# coqui-v0_2.net
KiCad netlist of a schematic drawn in EAGLE
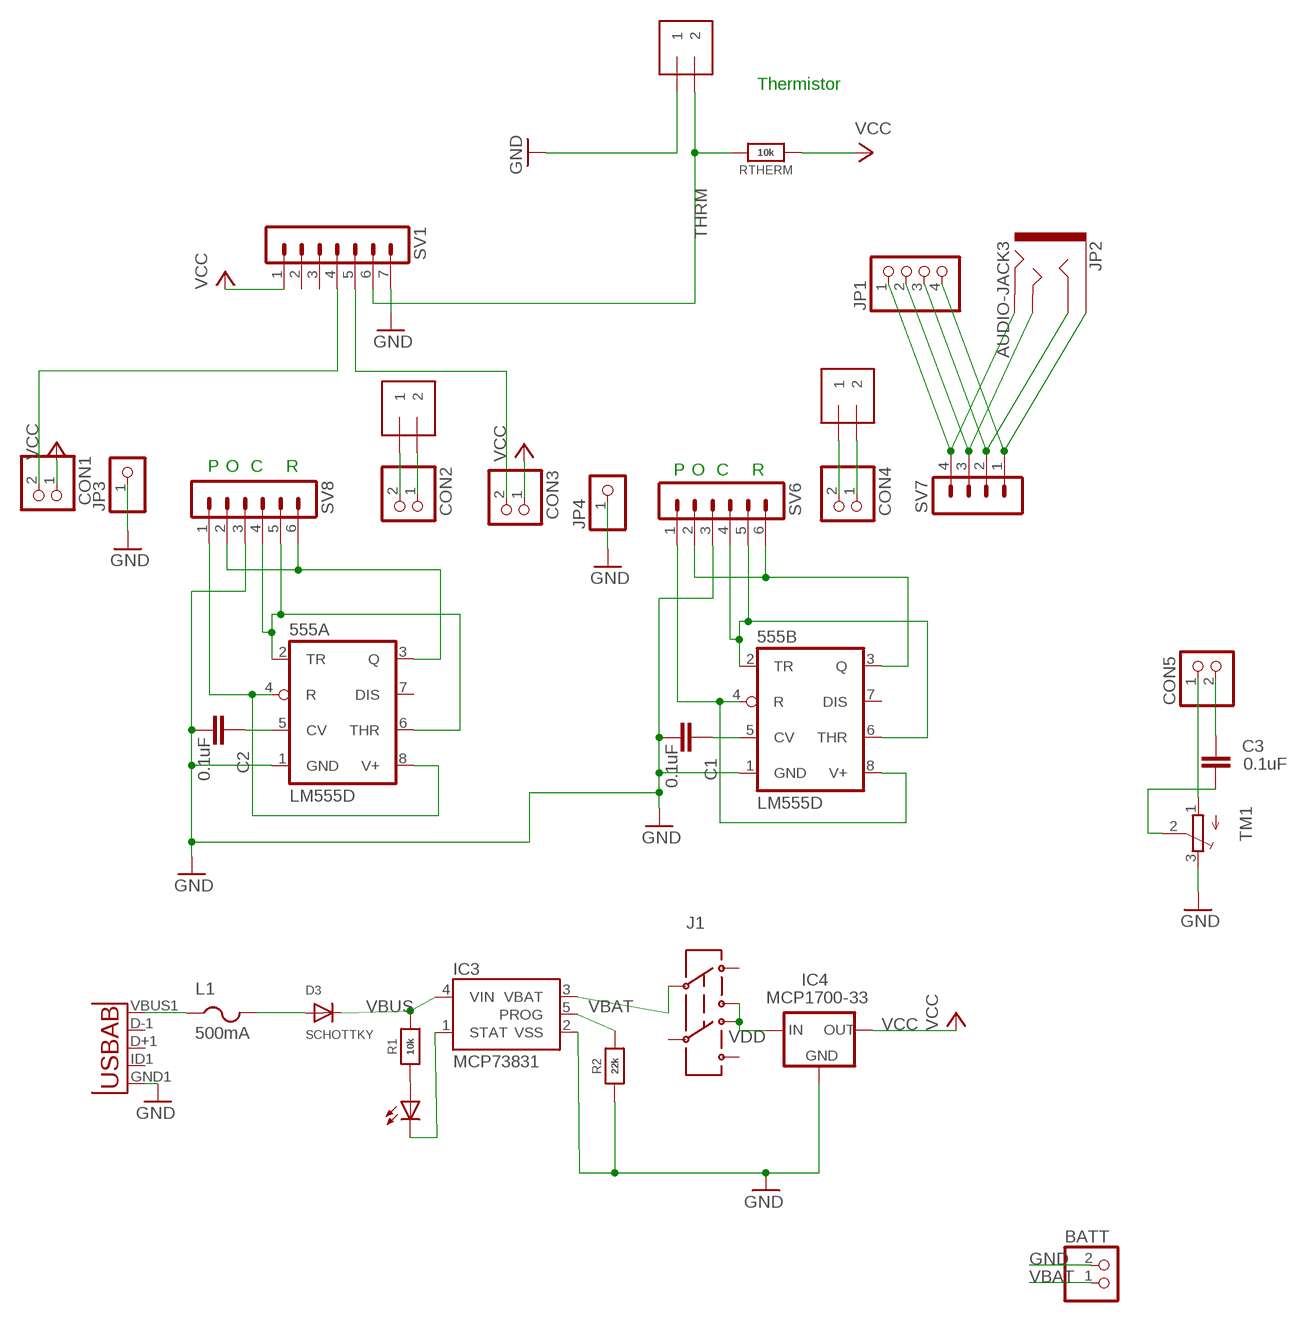
[diagram p0: schematic, sheet 1]

(export (version "E")
  (design (tool "Eeschema 10.0.6"))
  (components
    (comp (ref "555A")
      (value "LM555D")
      (footprint "eagle-import:SO08")
      (libsource (lib "eagle-import") (part "555DLM"))
    )
    (comp (ref "555B")
      (value "LM555D")
      (footprint "eagle-import:SO08")
      (libsource (lib "eagle-import") (part "555DLM"))
    )
    (comp (ref "BATT")
      (value "JST_2PIN-SMT-RA")
      (footprint "eagle-import:JST-PH-2-SMT-RA")
      (libsource (lib "eagle-import") (part "JST_2PIN-SMT-RA"))
    )
    (comp (ref "C1")
      (value "0.1uF")
      (footprint "eagle-import:0603-CAP")
      (libsource (lib "eagle-import") (part "CAP0603-CAP"))
    )
    (comp (ref "C2")
      (value "0.1uF")
      (footprint "eagle-import:0603-CAP")
      (libsource (lib "eagle-import") (part "CAP0603-CAP"))
    )
    (comp (ref "C3")
      (value "0.1uF")
      (footprint "eagle-import:0603-CAP")
      (libsource (lib "eagle-import") (part "CAP0603-CAP"))
    )
    (comp (ref "CHG")
      (value "0805")
      (footprint "eagle-import:CHIPLED_0805")
      (libsource (lib "eagle-import") (part "LEDCHIPLED_0805"))
    )
    (comp (ref "CON1")
      (value "PINHD-1X2")
      (footprint "eagle-import:1X02")
      (libsource (lib "eagle-import") (part "PINHD-1X2"))
    )
    (comp (ref "CON2")
      (value "PINHD-1X2")
      (footprint "eagle-import:1X02")
      (libsource (lib "eagle-import") (part "PINHD-1X2"))
    )
    (comp (ref "CON3")
      (value "PINHD-1X2")
      (footprint "eagle-import:1X02")
      (libsource (lib "eagle-import") (part "PINHD-1X2"))
    )
    (comp (ref "CON4")
      (value "PINHD-1X2")
      (footprint "eagle-import:1X02")
      (libsource (lib "eagle-import") (part "PINHD-1X2"))
    )
    (comp (ref "CON5")
      (value "PINHD-1X2")
      (footprint "eagle-import:1X02")
      (libsource (lib "eagle-import") (part "PINHD-1X2"))
    )
    (comp (ref "D3")
      (value "SCHOTTKY")
      (footprint "eagle-import:SOD-123FL")
      (libsource (lib "eagle-import") (part "DIODE_SOD-123FL"))
    )
    (comp (ref "IC3")
      (value "MCP73831")
      (footprint "eagle-import:SOT23-5")
      (libsource (lib "eagle-import") (part "MCP73831"))
    )
    (comp (ref "IC4")
      (value "MCP1700-33")
      (footprint "eagle-import:SOT89")
      (libsource (lib "eagle-import") (part "MCP1700SOT89"))
    )
    (comp (ref "IN1")
      (value "1X2-3.5MM")
      (footprint "eagle-import:1X2-3.5MM")
      (libsource (lib "eagle-import") (part "1X2-3.5MM"))
    )
    (comp (ref "IN2")
      (value "1X2-3.5MM")
      (footprint "eagle-import:1X2-3.5MM")
      (libsource (lib "eagle-import") (part "1X2-3.5MM"))
    )
    (comp (ref "J1")
      (value "AYZ0202")
      (footprint "eagle-import:AYZ0202")
      (libsource (lib "eagle-import") (part "AYZ0202"))
    )
    (comp (ref "JP1")
      (value "PINHD-1X4/90")
      (footprint "eagle-import:1X04_90")
      (libsource (lib "eagle-import") (part "PINHD-1X4/90"))
    )
    (comp (ref "JP2")
      (value "AUDIO-JACK3")
      (footprint "eagle-import:AUDIO-JACK-TRRS-SMD")
      (libsource (lib "eagle-import") (part "AUDIO-JACK3"))
    )
    (comp (ref "JP3")
      (value "PINHD-1X1")
      (footprint "eagle-import:1X01")
      (libsource (lib "eagle-import") (part "PINHD-1X1"))
    )
    (comp (ref "JP4")
      (value "PINHD-1X1")
      (footprint "eagle-import:1X01")
      (libsource (lib "eagle-import") (part "PINHD-1X1"))
    )
    (comp (ref "L1")
      (value "500mA")
      (footprint "eagle-import:R1206")
      (libsource (lib "eagle-import") (part "PTCFUSE-1206"))
    )
    (comp (ref "R1")
      (value "10k")
      (footprint "eagle-import:0603-NO")
      (libsource (lib "eagle-import") (part "RESISTOR_0603_NOOUT"))
    )
    (comp (ref "R2")
      (value "22k")
      (footprint "eagle-import:0603-NO")
      (libsource (lib "eagle-import") (part "RESISTOR_0603_NOOUT"))
    )
    (comp (ref "RTHERM")
      (value "10k")
      (footprint "eagle-import:0603-NO")
      (libsource (lib "eagle-import") (part "RESISTOR_0603_NOOUT"))
    )
    (comp (ref "SV1")
      (value "MA07-1")
      (footprint "eagle-import:MA07-1")
      (libsource (lib "eagle-import") (part "MA07-1"))
    )
    (comp (ref "SV6")
      (value "MA06-1")
      (footprint "eagle-import:MA06-1")
      (libsource (lib "eagle-import") (part "MA06-1"))
    )
    (comp (ref "SV7")
      (value "MA04-1")
      (footprint "eagle-import:MA04-1")
      (libsource (lib "eagle-import") (part "MA04-1"))
    )
    (comp (ref "SV8")
      (value "MA06-1")
      (footprint "eagle-import:MA06-1")
      (libsource (lib "eagle-import") (part "MA06-1"))
    )
    (comp (ref "THRM")
      (value "1X2-3.5MM")
      (footprint "eagle-import:1X2-3.5MM")
      (libsource (lib "eagle-import") (part "1X2-3.5MM"))
    )
    (comp (ref "TM1")
      (value "TRIMPOTTC33X")
      (footprint "eagle-import:TC33X")
      (libsource (lib "eagle-import") (part "TRIMPOTTC33X"))
    )
    (comp (ref "U$4")
      (value "USB-AB\"\"")
      (footprint "eagle-import:USB-AB-MICRO-SMD_V02_BOSS")
      (libsource (lib "eagle-import") (part "USB-AB{dblquote}{dblquote}"))
    )
  )
  (nets
    (net (code "1") (name "/THRM") (class "Default")
      (node (ref "RTHERM") (pin "2") (pinfunction "2_2") (pintype "passive"))
      (node (ref "SV1") (pin "6") (pinfunction "6_6") (pintype "passive"))
      (node (ref "THRM") (pin "2") (pinfunction "2_2") (pintype "passive"))
    )
    (net (code "2") (name "/VBAT") (class "Default")
      (node (ref "BATT") (pin "1") (pinfunction "2_1") (pintype "passive"))
      (node (ref "IC3") (pin "3") (pinfunction "VBAT_3") (pintype "power_in"))
      (node (ref "J1") (pin "2") (pinfunction "2_2") (pintype "bidirectional"))
    )
    (net (code "3") (name "/VBUS") (class "Default")
      (node (ref "D3") (pin "C") (pinfunction "C_C") (pintype "passive"))
      (node (ref "IC3") (pin "4") (pinfunction "VIN_4") (pintype "power_in"))
      (node (ref "R1") (pin "2") (pinfunction "2_2") (pintype "passive"))
    )
    (net (code "4") (name "/VDD") (class "Default")
      (node (ref "IC4") (pin "2") (pinfunction "IN_2") (pintype "input"))
      (node (ref "J1") (pin "1") (pinfunction "3_1") (pintype "bidirectional"))
      (node (ref "J1") (pin "6") (pinfunction "4_6") (pintype "bidirectional"))
    )
    (net (code "5") (name "GND") (class "Default")
      (node (ref "555A") (pin "1") (pinfunction "GND_1") (pintype "power_in"))
      (node (ref "555B") (pin "1") (pinfunction "GND_1") (pintype "power_in"))
      (node (ref "BATT") (pin "2") (pinfunction "1_2") (pintype "passive"))
      (node (ref "C1") (pin "1") (pinfunction "1_1") (pintype "passive"))
      (node (ref "C2") (pin "1") (pinfunction "1_1") (pintype "passive"))
      (node (ref "IC3") (pin "2") (pinfunction "VSS_2") (pintype "power_in"))
      (node (ref "IC4") (pin "1") (pinfunction "GND_1") (pintype "input"))
      (node (ref "JP3") (pin "1") (pinfunction "1_1") (pintype "passive"))
      (node (ref "JP4") (pin "1") (pinfunction "1_1") (pintype "passive"))
      (node (ref "R2") (pin "1") (pinfunction "1_1") (pintype "passive"))
      (node (ref "SV1") (pin "7") (pinfunction "7_7") (pintype "passive"))
      (node (ref "SV6") (pin "3") (pinfunction "3_3") (pintype "passive"))
      (node (ref "SV8") (pin "3") (pinfunction "3_3") (pintype "passive"))
      (node (ref "THRM") (pin "1") (pinfunction "1_1") (pintype "passive"))
      (node (ref "TM1") (pin "3") (pinfunction "E_3") (pintype "passive"))
      (node (ref "U$4") (pin "GND1") (pinfunction "GND_GND1") (pintype "bidirectional"))
    )
    (net (code "6") (name "Net-(555A-CV)") (class "Default")
      (node (ref "555A") (pin "5") (pinfunction "CV_5") (pintype "input"))
      (node (ref "C2") (pin "2") (pinfunction "2_2") (pintype "passive"))
    )
    (net (code "7") (name "Net-(555A-Q)") (class "Default")
      (node (ref "555A") (pin "3") (pinfunction "Q_3") (pintype "output"))
      (node (ref "SV8") (pin "2") (pinfunction "2_2") (pintype "passive"))
      (node (ref "SV8") (pin "6") (pinfunction "6_6") (pintype "passive"))
    )
    (net (code "8") (name "Net-(555A-R)") (class "Default")
      (node (ref "555A") (pin "4") (pinfunction "R_4") (pintype "input"))
      (node (ref "555A") (pin "8") (pinfunction "V+_8") (pintype "power_in"))
      (node (ref "SV8") (pin "1") (pinfunction "1_1") (pintype "passive"))
    )
    (net (code "9") (name "Net-(555A-THR)") (class "Default")
      (node (ref "555A") (pin "2") (pinfunction "TR_2") (pintype "input"))
      (node (ref "555A") (pin "6") (pinfunction "THR_6") (pintype "input"))
      (node (ref "SV8") (pin "4") (pinfunction "4_4") (pintype "passive"))
      (node (ref "SV8") (pin "5") (pinfunction "5_5") (pintype "passive"))
    )
    (net (code "10") (name "Net-(555B-CV)") (class "Default")
      (node (ref "555B") (pin "5") (pinfunction "CV_5") (pintype "input"))
      (node (ref "C1") (pin "2") (pinfunction "2_2") (pintype "passive"))
    )
    (net (code "11") (name "Net-(555B-Q)") (class "Default")
      (node (ref "555B") (pin "3") (pinfunction "Q_3") (pintype "output"))
      (node (ref "SV6") (pin "2") (pinfunction "2_2") (pintype "passive"))
      (node (ref "SV6") (pin "6") (pinfunction "6_6") (pintype "passive"))
    )
    (net (code "12") (name "Net-(555B-R)") (class "Default")
      (node (ref "555B") (pin "4") (pinfunction "R_4") (pintype "input"))
      (node (ref "555B") (pin "8") (pinfunction "V+_8") (pintype "power_in"))
      (node (ref "SV6") (pin "1") (pinfunction "1_1") (pintype "passive"))
    )
    (net (code "13") (name "Net-(555B-THR)") (class "Default")
      (node (ref "555B") (pin "2") (pinfunction "TR_2") (pintype "input"))
      (node (ref "555B") (pin "6") (pinfunction "THR_6") (pintype "input"))
      (node (ref "SV6") (pin "4") (pinfunction "4_4") (pintype "passive"))
      (node (ref "SV6") (pin "5") (pinfunction "5_5") (pintype "passive"))
    )
    (net (code "14") (name "Net-(C3-Pad2)") (class "Default")
      (node (ref "C3") (pin "2") (pinfunction "2_2") (pintype "passive"))
      (node (ref "CON5") (pin "2") (pinfunction "2_2") (pintype "passive"))
    )
    (net (code "15") (name "Net-(CHG-PadA)") (class "Default")
      (node (ref "CHG") (pin "A") (pinfunction "A_A") (pintype "passive"))
      (node (ref "R1") (pin "1") (pinfunction "1_1") (pintype "passive"))
    )
    (net (code "16") (name "Net-(CON1-Pad2)") (class "Default")
      (node (ref "CON1") (pin "2") (pinfunction "2_2") (pintype "passive"))
      (node (ref "SV1") (pin "4") (pinfunction "4_4") (pintype "passive"))
    )
    (net (code "17") (name "Net-(CON2-Pad1)") (class "Default")
      (node (ref "CON2") (pin "1") (pinfunction "1_1") (pintype "passive"))
      (node (ref "IN1") (pin "2") (pinfunction "2_2") (pintype "passive"))
    )
    (net (code "18") (name "Net-(CON2-Pad2)") (class "Default")
      (node (ref "CON2") (pin "2") (pinfunction "2_2") (pintype "passive"))
      (node (ref "IN1") (pin "1") (pinfunction "1_1") (pintype "passive"))
    )
    (net (code "19") (name "Net-(CON3-Pad2)") (class "Default")
      (node (ref "CON3") (pin "2") (pinfunction "2_2") (pintype "passive"))
      (node (ref "SV1") (pin "5") (pinfunction "5_5") (pintype "passive"))
    )
    (net (code "20") (name "Net-(CON4-Pad1)") (class "Default")
      (node (ref "CON4") (pin "1") (pinfunction "1_1") (pintype "passive"))
      (node (ref "IN2") (pin "2") (pinfunction "2_2") (pintype "passive"))
    )
    (net (code "21") (name "Net-(CON4-Pad2)") (class "Default")
      (node (ref "CON4") (pin "2") (pinfunction "2_2") (pintype "passive"))
      (node (ref "IN2") (pin "1") (pinfunction "1_1") (pintype "passive"))
    )
    (net (code "22") (name "Net-(D3-PadA)") (class "Default")
      (node (ref "D3") (pin "A") (pinfunction "A_A") (pintype "passive"))
      (node (ref "L1") (pin "2") (pinfunction "2_2") (pintype "passive"))
    )
    (net (code "23") (name "Net-(IC3-PROG)") (class "Default")
      (node (ref "IC3") (pin "5") (pinfunction "PROG_5") (pintype "input"))
      (node (ref "R2") (pin "2") (pinfunction "2_2") (pintype "passive"))
    )
    (net (code "24") (name "Net-(IC3-STAT)") (class "Default")
      (node (ref "CHG") (pin "C") (pinfunction "C_C") (pintype "passive"))
      (node (ref "IC3") (pin "1") (pinfunction "STAT_1") (pintype "output"))
    )
    (net (code "25") (name "Net-(JP1-Pad1)") (class "Default")
      (node (ref "JP1") (pin "1") (pinfunction "1_1") (pintype "passive"))
      (node (ref "JP2") (pin "RING2") (pinfunction "RING2_RING2") (pintype "bidirectional"))
      (node (ref "SV7") (pin "4") (pinfunction "4_4") (pintype "passive"))
    )
    (net (code "26") (name "Net-(JP1-Pad2)") (class "Default")
      (node (ref "JP1") (pin "2") (pinfunction "2_2") (pintype "passive"))
      (node (ref "JP2") (pin "TIP") (pinfunction "TIP_TIP") (pintype "bidirectional"))
      (node (ref "SV7") (pin "3") (pinfunction "3_3") (pintype "passive"))
    )
    (net (code "27") (name "Net-(JP1-Pad3)") (class "Default")
      (node (ref "JP1") (pin "3") (pinfunction "3_3") (pintype "passive"))
      (node (ref "JP2") (pin "RING1") (pinfunction "RING1_RING1") (pintype "bidirectional"))
      (node (ref "SV7") (pin "2") (pinfunction "2_2") (pintype "passive"))
    )
    (net (code "28") (name "Net-(JP1-Pad4)") (class "Default")
      (node (ref "JP1") (pin "4") (pinfunction "4_4") (pintype "passive"))
      (node (ref "JP2") (pin "EARTH") (pinfunction "EARTH_EARTH") (pintype "bidirectional"))
      (node (ref "SV7") (pin "1") (pinfunction "1_1") (pintype "passive"))
    )
    (net (code "29") (name "Net-(TM1-A)") (class "Default")
      (node (ref "CON5") (pin "1") (pinfunction "1_1") (pintype "passive"))
      (node (ref "TM1") (pin "1") (pinfunction "A_1") (pintype "passive"))
    )
    (net (code "30") (name "Net-(TM1-S)") (class "Default")
      (node (ref "C3") (pin "1") (pinfunction "1_1") (pintype "passive"))
      (node (ref "TM1") (pin "2") (pinfunction "S_2") (pintype "passive"))
    )
    (net (code "31") (name "Net-(U$4-VBUS)") (class "Default")
      (node (ref "L1") (pin "1") (pinfunction "1_1") (pintype "passive"))
      (node (ref "U$4") (pin "VBUS1") (pinfunction "VBUS_VBUS1") (pintype "bidirectional"))
    )
    (net (code "32") (name "VCC") (class "Default")
      (node (ref "CON1") (pin "1") (pinfunction "1_1") (pintype "passive"))
      (node (ref "CON3") (pin "1") (pinfunction "1_1") (pintype "passive"))
      (node (ref "IC4") (pin "3") (pinfunction "OUT_3") (pintype "passive"))
      (node (ref "RTHERM") (pin "1") (pinfunction "1_1") (pintype "passive"))
      (node (ref "SV1") (pin "1") (pinfunction "1_1") (pintype "passive"))
    )
    (net (code "33") (name "unconnected-(555A-DIS-Pad7)") (class "Default")
      (node (ref "555A") (pin "7") (pinfunction "DIS_7") (pintype "input"))
    )
    (net (code "34") (name "unconnected-(555B-DIS-Pad7)") (class "Default")
      (node (ref "555B") (pin "7") (pinfunction "DIS_7") (pintype "input"))
    )
    (net (code "35") (name "unconnected-(J1-1-Pad3)") (class "Default")
      (node (ref "J1") (pin "3") (pinfunction "1_3") (pintype "bidirectional"))
    )
    (net (code "36") (name "unconnected-(J1-6-Pad4)") (class "Default")
      (node (ref "J1") (pin "4") (pinfunction "6_4") (pintype "bidirectional"))
    )
    (net (code "37") (name "unconnected-(J1-Pad5)") (class "Default")
      (node (ref "J1") (pin "5") (pinfunction "5_5") (pintype "bidirectional"))
    )
    (net (code "38") (name "unconnected-(SV1-Pad2)") (class "Default")
      (node (ref "SV1") (pin "2") (pinfunction "2_2") (pintype "passive"))
    )
    (net (code "39") (name "unconnected-(SV1-Pad3)") (class "Default")
      (node (ref "SV1") (pin "3") (pinfunction "3_3") (pintype "passive"))
    )
    (net (code "40") (name "unconnected-(U$4-D+-PadD+1)") (class "Default")
      (node (ref "U$4") (pin "D+1") (pinfunction "D+_D+1") (pintype "bidirectional"))
    )
    (net (code "41") (name "unconnected-(U$4-D--PadD-1)") (class "Default")
      (node (ref "U$4") (pin "D-1") (pinfunction "D-_D-1") (pintype "bidirectional"))
    )
    (net (code "42") (name "unconnected-(U$4-USBID-PadID1)") (class "Default")
      (node (ref "U$4") (pin "ID1") (pinfunction "USBID_ID1") (pintype "bidirectional"))
    )
  )
)
